# Test_Jig_Pixhawk_DUT.net
KiCad netlist of a schematic drawn in Altium Designer
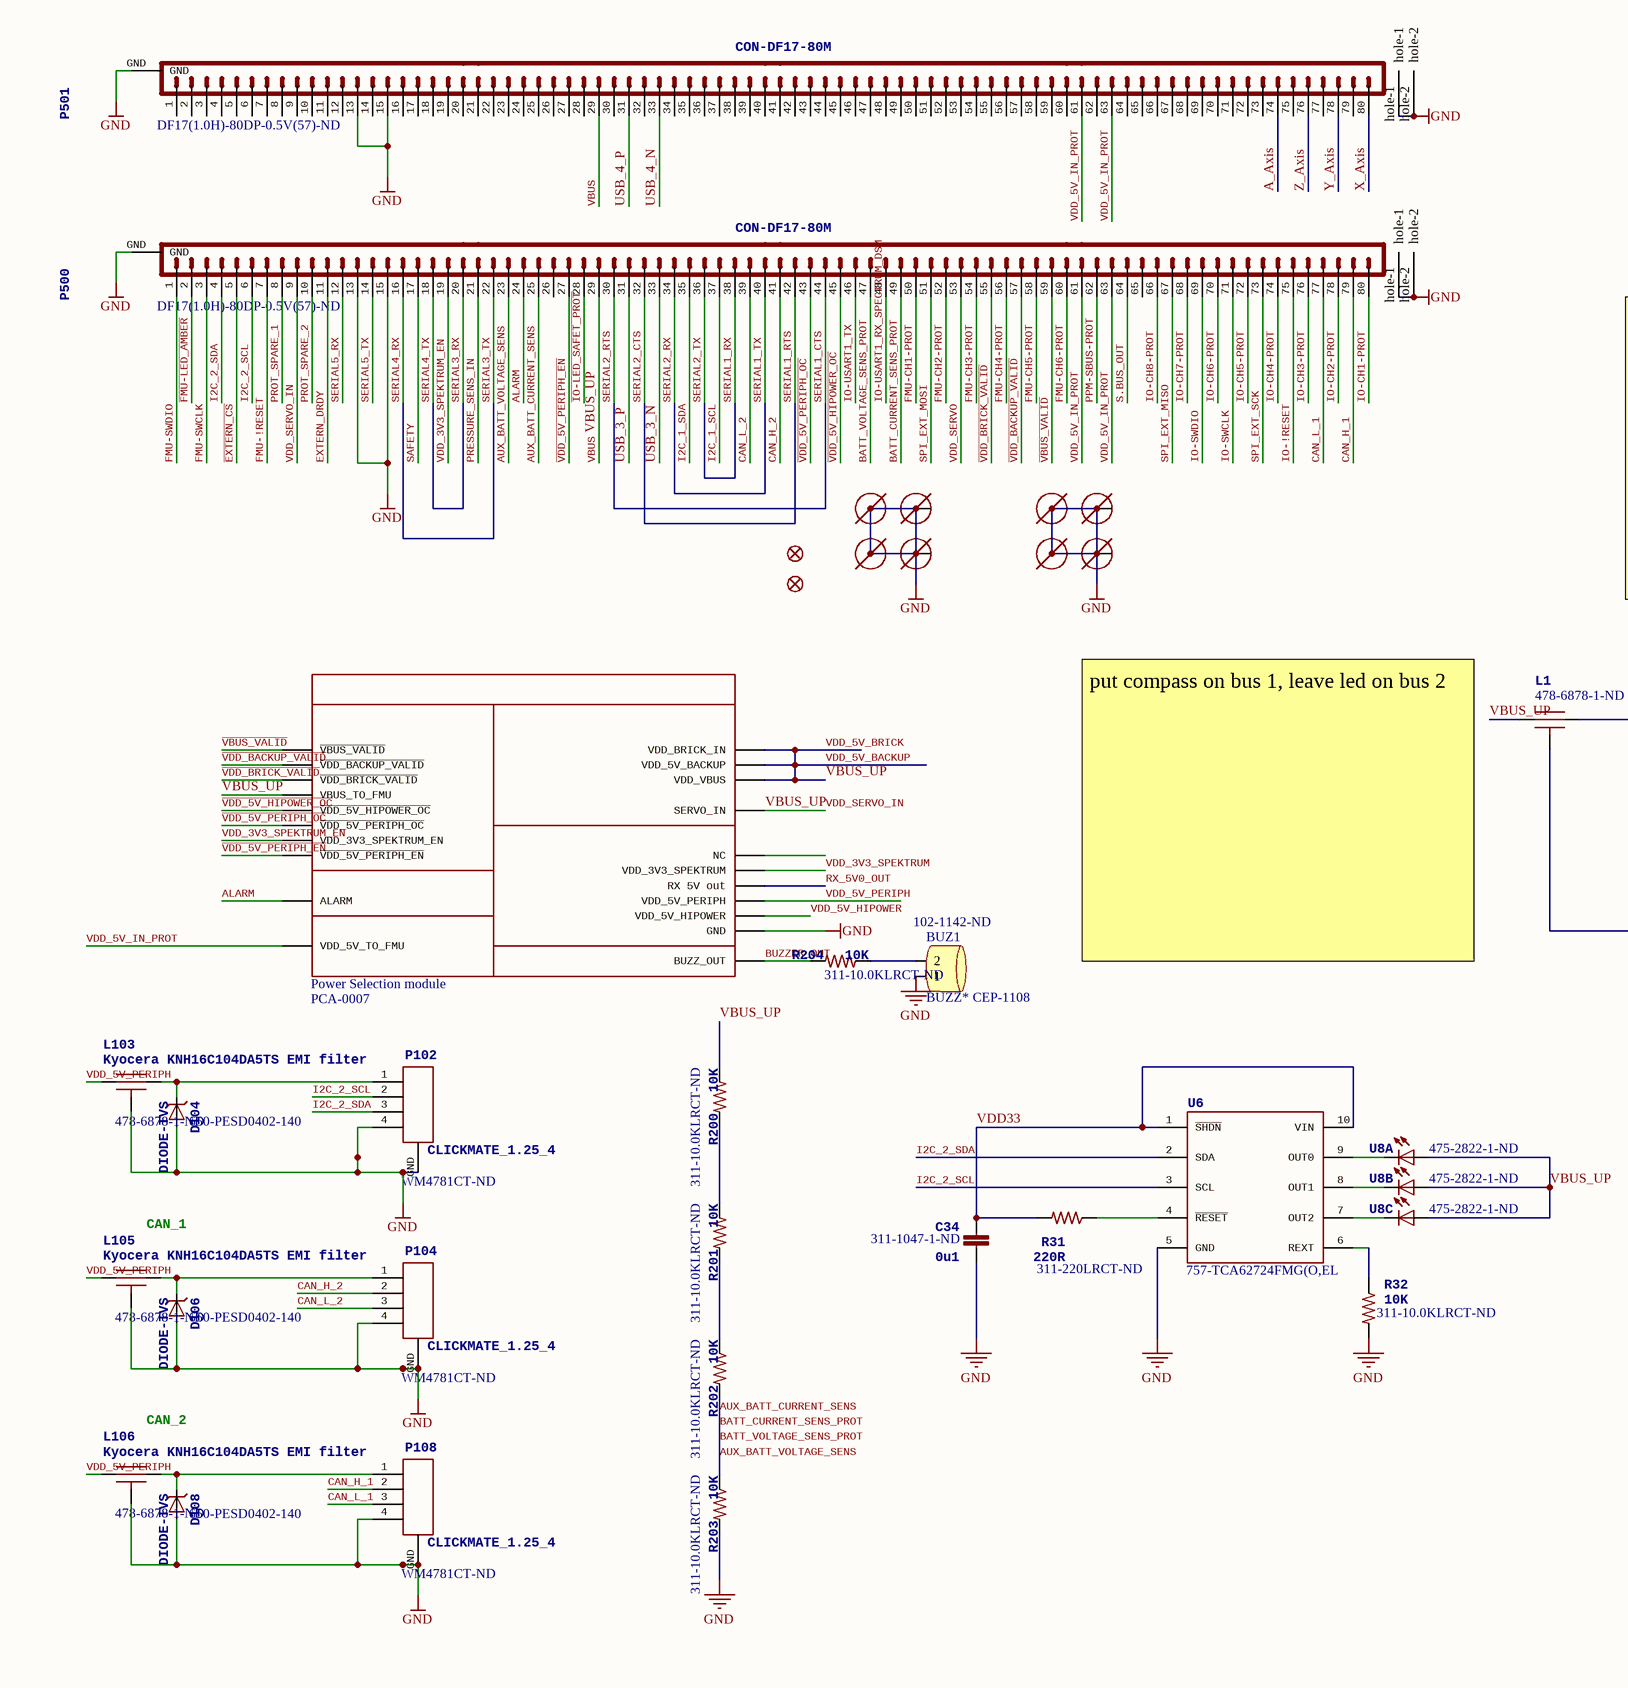
[diagram p0: Test_Jig_Pixhawk_DUT.SchDoc, left]
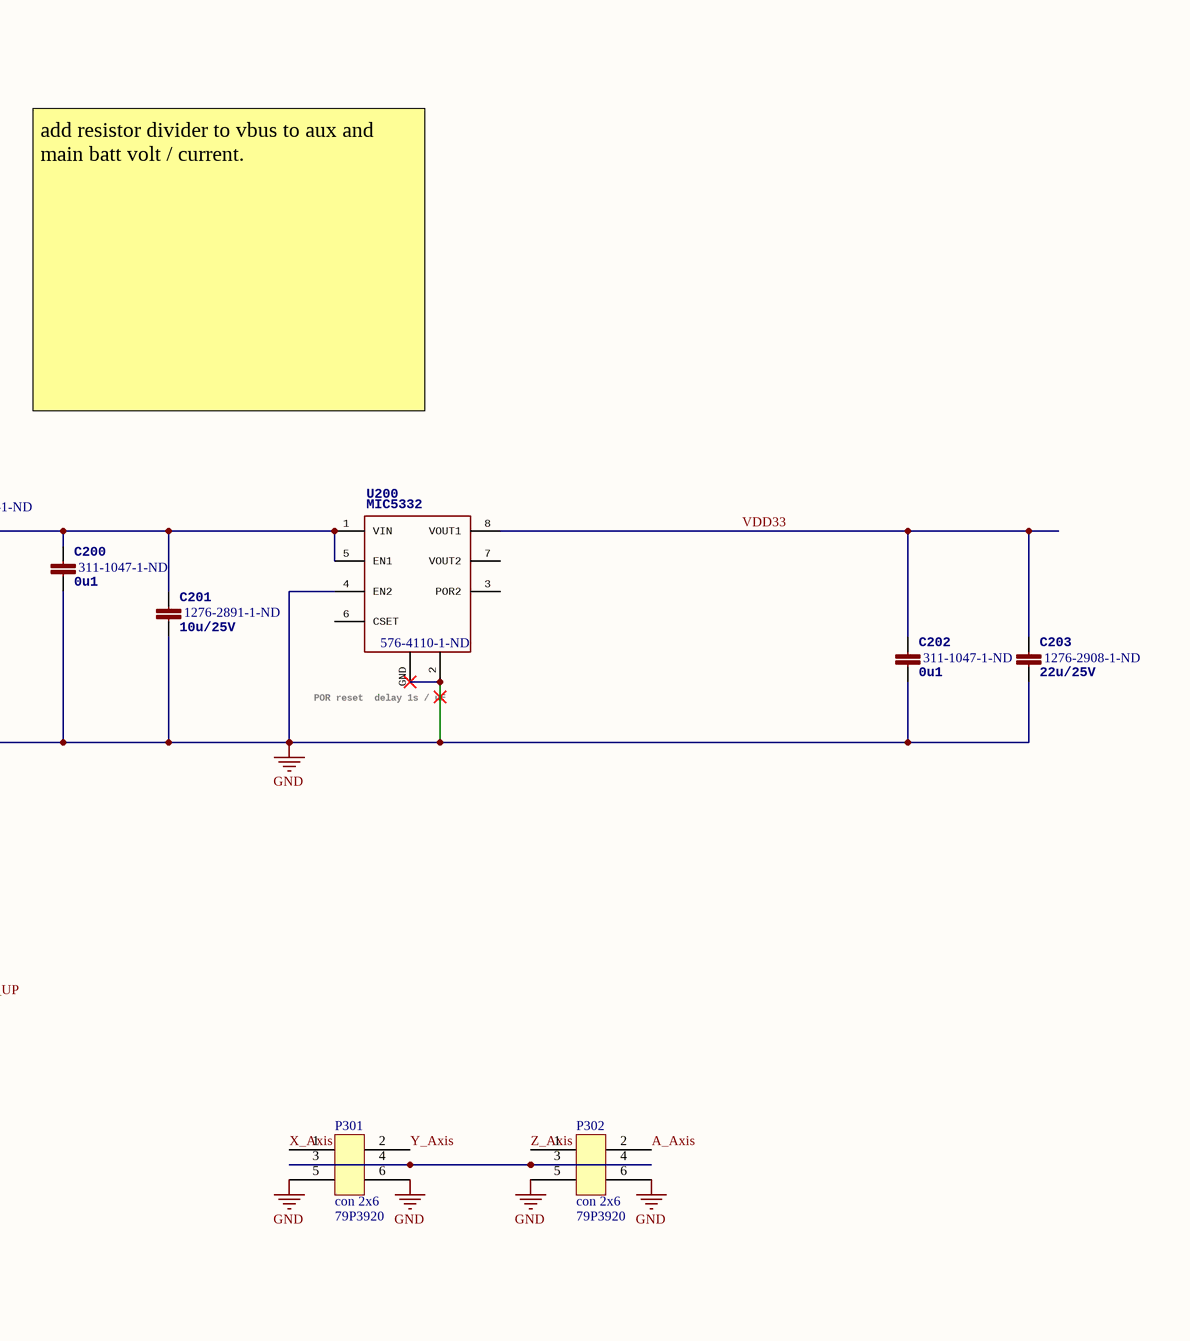
[diagram p1: Test_Jig_Pixhawk_DUT.SchDoc, right]

(export (version "E")
  (design (tool "Eeschema 10.0.6"))
  (components
    (comp (ref "BUZ1")
      (value "BUZZ* CEP-1108")
      (footprint "CEP-1108")
      (fields (field (name "MANUFACTURER") "CUI") (field (name "SUPPLIER PART NUMBER 1") "102-1142-ND"))
      (libsource (lib "LimeLab Integrated Lib R1") (part "BUZZ* CEP-1108"))
    )
    (comp (ref "C34")
      (value "0u1")
      (footprint "0402-CAP")
      (fields
        (field (name "PARTNO") "CC0402ZRY5V7BB104")
        (field (name "SUPPLIER PART NUMBER 1") "311-1047-1-ND")
      )
      (libsource (lib "pixhawk2") (part "CAP0402"))
    )
    (comp (ref "C200")
      (value "0u1")
      (footprint "0402-CAP")
      (fields (field (name "SUPPLIER PART NUMBER 1") "311-1047-1-ND"))
      (libsource (lib "") (part "CAP0402_1"))
    )
    (comp (ref "C201")
      (value "10u/25V")
      (footprint "0805-CAP")
      (fields (field (name "SUPPLIER PART NUMBER 1") "1276-2891-1-ND"))
      (libsource (lib "pixhawk2") (part "CAP0805"))
    )
    (comp (ref "C202")
      (value "0u1")
      (footprint "0402-CAP")
      (fields (field (name "SUPPLIER PART NUMBER 1") "311-1047-1-ND"))
      (libsource (lib "") (part "CAP0402_1"))
    )
    (comp (ref "C203")
      (value "22u/25V")
      (footprint "0805-CAP")
      (fields (field (name "SUPPLIER PART NUMBER 1") "1276-2908-1-ND"))
      (libsource (lib "pixhawk2") (part "CAP0805"))
    )
    (comp (ref "D104")
      (value "DIODE-TVS")
      (footprint "0402-TVS")
      (description "Diode, TVS, 14VWM, 40VC, 0402, SMD")
      (fields
        (field (name "SUPPLIER PART NUMBER 1") "650-PESD0402-140")
        (field (name "3DR_PARTNO") "ECM0837")
      )
      (libsource (lib "PCA_0005_FULL_CB_REV_A") (part "DIODE-TVS"))
    )
    (comp (ref "D106")
      (value "DIODE-TVS")
      (footprint "0402-TVS")
      (description "Diode, TVS, 14VWM, 40VC, 0402, SMD")
      (fields
        (field (name "SUPPLIER PART NUMBER 1") "650-PESD0402-140")
        (field (name "3DR_PARTNO") "ECM0837")
      )
      (libsource (lib "PCA_0005_FULL_CB_REV_A") (part "DIODE-TVS"))
    )
    (comp (ref "D108")
      (value "DIODE-TVS")
      (footprint "0402-TVS")
      (description "Diode, TVS, 14VWM, 40VC, 0402, SMD")
      (fields
        (field (name "SUPPLIER PART NUMBER 1") "650-PESD0402-140")
        (field (name "3DR_PARTNO") "ECM0837")
      )
      (libsource (lib "PCA_0005_FULL_CB_REV_A") (part "DIODE-TVS"))
    )
    (comp (ref "JP400")
      (value "FIDUCIAL1.5X3")
      (footprint "FIDUCIAL-1.5X3")
      (description "<b>Fiducial Alignment Points</b>\nVarious fiducial points for machine vision alignment.")
      (libsource (lib "pixhawk2") (part "FIDUCIAL1.5X3"))
    )
    (comp (ref "JP401")
      (value "FIDUCIAL1.5X3")
      (footprint "FIDUCIAL-1.5X3")
      (description "<b>Fiducial Alignment Points</b>\nVarious fiducial points for machine vision alignment.")
      (libsource (lib "pixhawk2") (part "FIDUCIAL1.5X3"))
    )
    (comp (ref "L1")
      (value "Kyocera KNH16C104DA5TS EMI filter")
      (footprint "KYOCERA-KNH16-DA")
      (fields (field (name "SUPPLIER PART NUMBER 1") "478-6878-1-ND"))
      (libsource (lib "pixhawk2") (part "KNH16C104DA5TS"))
    )
    (comp (ref "L103")
      (value "Kyocera KNH16C104DA5TS EMI filter")
      (footprint "KYOCERA-KNH16-DA")
      (description "Capacitor, Filter, 0.1uF, 25V, 2A, 0603, SMD")
      (fields (field (name "SUPPLIER PART NUMBER 1") "478-6878-1-ND") (field (name "3DR_PARTNO") "ECM0719"))
      (libsource (lib "PCA_0005_FULL_CB_REV_A") (part "KNH16C104DA5TS"))
    )
    (comp (ref "L105")
      (value "Kyocera KNH16C104DA5TS EMI filter")
      (footprint "KYOCERA-KNH16-DA")
      (description "Capacitor, Filter, 0.1uF, 25V, 2A, 0603, SMD")
      (fields (field (name "SUPPLIER PART NUMBER 1") "478-6878-1-ND") (field (name "3DR_PARTNO") "ECM0719"))
      (libsource (lib "PCA_0005_FULL_CB_REV_A") (part "KNH16C104DA5TS"))
    )
    (comp (ref "L106")
      (value "Kyocera KNH16C104DA5TS EMI filter")
      (footprint "KYOCERA-KNH16-DA")
      (description "Capacitor, Filter, 0.1uF, 25V, 2A, 0603, SMD")
      (fields (field (name "SUPPLIER PART NUMBER 1") "478-6878-1-ND") (field (name "3DR_PARTNO") "ECM0719"))
      (libsource (lib "PCA_0005_FULL_CB_REV_A") (part "KNH16C104DA5TS"))
    )
    (comp (ref "M3_MOUNT901")
      (value "MOUNT-HOLE1.8MM")
      (footprint "MOUNT-HOLE1.8")
      (libsource (lib "pixhawk2") (part "MOUNT-HOLE1.8MM"))
    )
    (comp (ref "M3_MOUNT902")
      (value "MOUNT-HOLE1.8MM")
      (footprint "MOUNT-HOLE1.8")
      (libsource (lib "pixhawk2") (part "MOUNT-HOLE1.8MM"))
    )
    (comp (ref "M3_MOUNT903")
      (value "MOUNT-HOLE1.8MM")
      (footprint "MOUNT-HOLE1.8")
      (libsource (lib "pixhawk2") (part "MOUNT-HOLE1.8MM"))
    )
    (comp (ref "M3_MOUNT904")
      (value "MOUNT-HOLE1.8MM")
      (footprint "MOUNT-HOLE1.8")
      (libsource (lib "pixhawk2") (part "MOUNT-HOLE1.8MM"))
    )
    (comp (ref "M3_MOUNT911")
      (value "MOUNT-HOLE1.8MM")
      (footprint "MOUNT-HOLE1.8")
      (libsource (lib "pixhawk2") (part "MOUNT-HOLE1.8MM"))
    )
    (comp (ref "M3_MOUNT912")
      (value "MOUNT-HOLE1.8MM")
      (footprint "MOUNT-HOLE1.8")
      (libsource (lib "pixhawk2") (part "MOUNT-HOLE1.8MM"))
    )
    (comp (ref "M3_MOUNT913")
      (value "MOUNT-HOLE1.8MM")
      (footprint "MOUNT-HOLE1.8")
      (libsource (lib "pixhawk2") (part "MOUNT-HOLE1.8MM"))
    )
    (comp (ref "M3_MOUNT914")
      (value "MOUNT-HOLE1.8MM")
      (footprint "MOUNT-HOLE1.8")
      (libsource (lib "pixhawk2") (part "MOUNT-HOLE1.8MM"))
    )
    (comp (ref "P102")
      (value "CLICKMATE_1.25_4")
      (footprint "CLICKMATE_V4")
      (description "Connector, Rcpt, 4Pos, 1.25MM, W/B, VERT, SMD, Tin")
      (fields (field (name "SUPPLIER PART NUMBER 1") "WM4781CT-ND") (field (name "3DR_PARTNO") "PRT0441"))
      (libsource (lib "PCA_0005_FULL_CB_REV_A") (part "CLICKMATE_1.25_4"))
    )
    (comp (ref "P104")
      (value "CLICKMATE_1.25_4")
      (footprint "CLICKMATE_V4")
      (description "Connector, Rcpt, 4Pos, 1.25MM, W/B, VERT, SMD, Tin")
      (fields (field (name "SUPPLIER PART NUMBER 1") "WM4781CT-ND") (field (name "3DR_PARTNO") "PRT0441"))
      (libsource (lib "PCA_0005_FULL_CB_REV_A") (part "CLICKMATE_1.25_4"))
    )
    (comp (ref "P108")
      (value "CLICKMATE_1.25_4")
      (footprint "CLICKMATE_V4")
      (description "Connector, Rcpt, 4Pos, 1.25MM, W/B, VERT, SMD, Tin")
      (fields (field (name "SUPPLIER PART NUMBER 1") "WM4781CT-ND") (field (name "3DR_PARTNO") "PRT0441"))
      (libsource (lib "PCA_0005_FULL_CB_REV_A") (part "CLICKMATE_1.25_4"))
    )
    (comp (ref "P301")
      (value "con 2x6")
      (footprint "TSW-103-07-G-D")
      (description "Connector, Header, 6Pos, 2.54MM, Vert, THT, Au")
      (fields (field (name "SUPPLIER PART NUMBER 1") "79P3920") (field (name "3DR_PARTNO") "PRT0445"))
      (libsource (lib "PCA_0005_FULL_CB_REV_A") (part "con 2x6"))
    )
    (comp (ref "P302")
      (value "con 2x6")
      (footprint "TSW-103-07-G-D")
      (description "Connector, Header, 6Pos, 2.54MM, Vert, THT, Au")
      (fields (field (name "SUPPLIER PART NUMBER 1") "79P3920") (field (name "3DR_PARTNO") "PRT0445"))
      (libsource (lib "PCA_0005_FULL_CB_REV_A") (part "con 2x6"))
    )
    (comp (ref "P500")
      (value "CON-DF17-80M")
      (footprint "CON-DF17-80M")
      (description "Connector, Header, 80Pos, .5MM, DUAL, SMD, Au")
      (fields
        (field (name "SUPPLIER PART NUMBER 1") "DF17(1.0H)-80DP-0.5V(57)-ND")
        (field (name "3DR_PARTNO") "PRT0436")
      )
      (libsource (lib "PCA_0005_FULL_CB_REV_A") (part "CON-DF17-80M"))
    )
    (comp (ref "P501")
      (value "CON-DF17-80M")
      (footprint "CON-DF17-80M")
      (description "Connector, Header, 80Pos, .5MM, DUAL, SMD, Au")
      (fields
        (field (name "SUPPLIER PART NUMBER 1") "DF17(1.0H)-80DP-0.5V(57)-ND")
        (field (name "3DR_PARTNO") "PRT0436")
      )
      (libsource (lib "PCA_0005_FULL_CB_REV_A") (part "CON-DF17-80M"))
    )
    (comp (ref "PSM200")
      (value "Power Selection module")
      (footprint "PSM")
      (description "PCA, PSM, PX4, Assembly")
      (fields (field (name "SUPPLIER PART NUMBER 1") "PCA-0007") (field (name "3DR_PARTNO") "PCA0007"))
      (libsource (lib "PCA_0005_FULL_CB_REV_A") (part "PSMPSM"))
    )
    (comp (ref "R31")
      (value "220R")
      (footprint "0402-RES")
      (fields (field (name "SUPPLIER PART NUMBER 1") "311-220LRCT-ND"))
      (libsource (lib "pixhawk2") (part "RESISTOR0402-RES"))
    )
    (comp (ref "R32")
      (value "10K")
      (footprint "0402-RES")
      (fields
        (field (name "PARTNO") "RC0402FR-0710KL")
        (field (name "SUPPLIER PART NUMBER 1") "311-10.0KLRCT-ND")
      )
      (libsource (lib "pixhawk2") (part "RESISTOR0402-RES"))
    )
    (comp (ref "R200")
      (value "10K")
      (footprint "0402-RES")
      (description "RES 10K OHM 1/16W 1% 0402 SMD")
      (fields
        (field (name "PARTNO") "RC0402FR-0710KL")
        (field (name "SUPPLIER PART NUMBER 1") "311-10.0KLRCT-ND")
        (field (name "3DR_PARTNO") "ECM0800")
      )
      (libsource (lib "pixhawk2") (part "RESISTOR0402-RES"))
    )
    (comp (ref "R201")
      (value "10K")
      (footprint "0402-RES")
      (description "RES 10K OHM 1/16W 1% 0402 SMD")
      (fields
        (field (name "PARTNO") "RC0402FR-0710KL")
        (field (name "SUPPLIER PART NUMBER 1") "311-10.0KLRCT-ND")
        (field (name "3DR_PARTNO") "ECM0800")
      )
      (libsource (lib "pixhawk2") (part "RESISTOR0402-RES"))
    )
    (comp (ref "R202")
      (value "10K")
      (footprint "0402-RES")
      (description "RES 10K OHM 1/16W 1% 0402 SMD")
      (fields
        (field (name "PARTNO") "RC0402FR-0710KL")
        (field (name "SUPPLIER PART NUMBER 1") "311-10.0KLRCT-ND")
        (field (name "3DR_PARTNO") "ECM0800")
      )
      (libsource (lib "pixhawk2") (part "RESISTOR0402-RES"))
    )
    (comp (ref "R203")
      (value "10K")
      (footprint "0402-RES")
      (description "RES 10K OHM 1/16W 1% 0402 SMD")
      (fields
        (field (name "PARTNO") "RC0402FR-0710KL")
        (field (name "SUPPLIER PART NUMBER 1") "311-10.0KLRCT-ND")
        (field (name "3DR_PARTNO") "ECM0800")
      )
      (libsource (lib "pixhawk2") (part "RESISTOR0402-RES"))
    )
    (comp (ref "R204")
      (value "10K")
      (footprint "0402-RES")
      (description "RES 10K OHM 1/16W 1% 0402 SMD")
      (fields
        (field (name "PARTNO") "RC0402FR-0710KL")
        (field (name "SUPPLIER PART NUMBER 1") "311-10.0KLRCT-ND")
        (field (name "3DR_PARTNO") "ECM0800")
      )
      (libsource (lib "pixhawk2") (part "RESISTOR0402-RES"))
    )
    (comp (ref "U6")
      (value "TCA62724FMG")
      (footprint "SON10")
      (description "Toshiba TCA62724FMG I2C RGB LED driver")
      (fields (field (name "SUPPLIER PART NUMBER 1") "757-TCA62724FMG(O,EL"))
      (libsource (lib "pixhawk2") (part "TCA62724FMG"))
    )
    (comp (ref "U8")
      (value "LRTB GFTG-T7AW-1+V7A7-29+R5T9-49-L")
      (footprint "6-PLCC")
      (description "RGB LED with separate anode/cathode terminals")
      (fields (field (name "SUPPLIER PART NUMBER 1") "475-2822-1-ND"))
      (libsource (lib "pixhawk2") (part "RGB-LED6-PLCC"))
    )
    (comp (ref "U200")
      (value "MIC5332")
      (footprint "MLF-8-EPAD")
      (fields (field (name "SUPPLIER PART NUMBER 1") "576-4110-1-ND"))
      (libsource (lib "pixhawk2") (part "MIC5332"))
    )
  )
  (nets
    (net (code "1") (name "/ALARM") (class "Default")
      (node (ref "P500") (pin "24") (pinfunction "24_24") (pintype "passive"))
      (node (ref "PSM200") (pin "ALARM") (pinfunction "ALARM_ALARM") (pintype "passive"))
    )
    (net (code "2") (name "/AUX_BATT_CURRENT_SENS") (class "Default")
      (node (ref "P500") (pin "23") (pinfunction "23_23") (pintype "passive"))
      (node (ref "P500") (pin "25") (pinfunction "25_25") (pintype "passive"))
      (node (ref "P500") (pin "47") (pinfunction "47_47") (pintype "passive"))
      (node (ref "P500") (pin "49") (pinfunction "49_49") (pintype "passive"))
      (node (ref "R202") (pin "P$2") (pinfunction "2_P$2") (pintype "passive"))
      (node (ref "R203") (pin "P$1") (pinfunction "1_P$1") (pintype "passive"))
    )
    (net (code "3") (name "/A_Axis") (class "Default")
      (node (ref "P302") (pin "2") (pinfunction "2_2") (pintype "passive"))
      (node (ref "P501") (pin "74") (pinfunction "74_74") (pintype "passive"))
    )
    (net (code "4") (name "/BUZZER_OUT") (class "Default")
      (node (ref "PSM200") (pin "BUZZER_OUT") (pinfunction "BUZZ_OUT_BUZZER_OUT") (pintype "passive"))
      (node (ref "R204") (pin "P$2") (pinfunction "2_P$2") (pintype "passive"))
    )
    (net (code "5") (name "/CAN_H_1") (class "Default")
      (node (ref "P108") (pin "2") (pinfunction "2_2") (pintype "passive"))
      (node (ref "P500") (pin "79") (pinfunction "79_79") (pintype "passive"))
    )
    (net (code "6") (name "/CAN_H_2") (class "Default")
      (node (ref "P104") (pin "2") (pinfunction "2_2") (pintype "passive"))
      (node (ref "P500") (pin "41") (pinfunction "41_41") (pintype "passive"))
    )
    (net (code "7") (name "/CAN_L_1") (class "Default")
      (node (ref "P108") (pin "3") (pinfunction "3_3") (pintype "passive"))
      (node (ref "P500") (pin "77") (pinfunction "77_77") (pintype "passive"))
    )
    (net (code "8") (name "/CAN_L_2") (class "Default")
      (node (ref "P104") (pin "3") (pinfunction "3_3") (pintype "passive"))
      (node (ref "P500") (pin "39") (pinfunction "39_39") (pintype "passive"))
    )
    (net (code "9") (name "/EXTERN_DRDY") (class "Default")
      (node (ref "P500") (pin "11") (pinfunction "11_11") (pintype "passive"))
    )
    (net (code "10") (name "/FMU-!RESET") (class "Default")
      (node (ref "P500") (pin "7") (pinfunction "7_7") (pintype "passive"))
    )
    (net (code "11") (name "/FMU-CH1-PROT") (class "Default")
      (node (ref "P500") (pin "50") (pinfunction "50_50") (pintype "passive"))
    )
    (net (code "12") (name "/FMU-CH2-PROT") (class "Default")
      (node (ref "P500") (pin "52") (pinfunction "52_52") (pintype "passive"))
    )
    (net (code "13") (name "/FMU-CH3-PROT") (class "Default")
      (node (ref "P500") (pin "54") (pinfunction "54_54") (pintype "passive"))
    )
    (net (code "14") (name "/FMU-CH4-PROT") (class "Default")
      (node (ref "P500") (pin "56") (pinfunction "56_56") (pintype "passive"))
    )
    (net (code "15") (name "/FMU-CH5-PROT") (class "Default")
      (node (ref "P500") (pin "58") (pinfunction "58_58") (pintype "passive"))
    )
    (net (code "16") (name "/FMU-CH6-PROT") (class "Default")
      (node (ref "P500") (pin "60") (pinfunction "60_60") (pintype "passive"))
    )
    (net (code "17") (name "/FMU-SWCLK") (class "Default")
      (node (ref "P500") (pin "3") (pinfunction "3_3") (pintype "passive"))
    )
    (net (code "18") (name "/FMU-SWDIO") (class "Default")
      (node (ref "P500") (pin "1") (pinfunction "1_1") (pintype "passive"))
    )
    (net (code "19") (name "/I2C_1_SCL") (class "Default")
      (node (ref "P500") (pin "37") (pinfunction "37_37") (pintype "passive"))
    )
    (net (code "20") (name "/I2C_1_SDA") (class "Default")
      (node (ref "P500") (pin "35") (pinfunction "35_35") (pintype "passive"))
    )
    (net (code "21") (name "/I2C_2_SCL") (class "Default")
      (node (ref "P102") (pin "2") (pinfunction "2_2") (pintype "passive"))
      (node (ref "P500") (pin "6") (pinfunction "6_6") (pintype "passive"))
      (node (ref "U6") (pin "3") (pinfunction "SCL_3") (pintype "passive"))
    )
    (net (code "22") (name "/I2C_2_SDA") (class "Default")
      (node (ref "P102") (pin "3") (pinfunction "3_3") (pintype "passive"))
      (node (ref "P500") (pin "4") (pinfunction "4_4") (pintype "passive"))
      (node (ref "U6") (pin "2") (pinfunction "SDA_2") (pintype "passive"))
    )
    (net (code "23") (name "/IO-!RESET") (class "Default")
      (node (ref "P500") (pin "75") (pinfunction "75_75") (pintype "passive"))
    )
    (net (code "24") (name "/IO-CH1-PROT") (class "Default")
      (node (ref "P500") (pin "80") (pinfunction "80_80") (pintype "passive"))
    )
    (net (code "25") (name "/IO-CH2-PROT") (class "Default")
      (node (ref "P500") (pin "78") (pinfunction "78_78") (pintype "passive"))
    )
    (net (code "26") (name "/IO-CH3-PROT") (class "Default")
      (node (ref "P500") (pin "76") (pinfunction "76_76") (pintype "passive"))
    )
    (net (code "27") (name "/IO-CH4-PROT") (class "Default")
      (node (ref "P500") (pin "74") (pinfunction "74_74") (pintype "passive"))
    )
    (net (code "28") (name "/IO-CH5-PROT") (class "Default")
      (node (ref "P500") (pin "72") (pinfunction "72_72") (pintype "passive"))
    )
    (net (code "29") (name "/IO-CH6-PROT") (class "Default")
      (node (ref "P500") (pin "70") (pinfunction "70_70") (pintype "passive"))
    )
    (net (code "30") (name "/IO-CH7-PROT") (class "Default")
      (node (ref "P500") (pin "68") (pinfunction "68_68") (pintype "passive"))
    )
    (net (code "31") (name "/IO-CH8-PROT") (class "Default")
      (node (ref "P500") (pin "66") (pinfunction "66_66") (pintype "passive"))
    )
    (net (code "32") (name "/IO-SWCLK") (class "Default")
      (node (ref "P500") (pin "71") (pinfunction "71_71") (pintype "passive"))
    )
    (net (code "33") (name "/IO-SWDIO") (class "Default")
      (node (ref "P500") (pin "69") (pinfunction "69_69") (pintype "passive"))
    )
    (net (code "34") (name "/IO-USART1_RX_SPECTRUM_DSM") (class "Default")
      (node (ref "P500") (pin "48") (pinfunction "48_48") (pintype "passive"))
    )
    (net (code "35") (name "/IO-USART1_TX") (class "Default")
      (node (ref "P500") (pin "46") (pinfunction "46_46") (pintype "passive"))
    )
    (net (code "36") (name "/PPM-SBUS-PROT") (class "Default")
      (node (ref "P500") (pin "62") (pinfunction "62_62") (pintype "passive"))
    )
    (net (code "37") (name "/PRESSURE_SENS_IN") (class "Default")
      (node (ref "P500") (pin "21") (pinfunction "21_21") (pintype "passive"))
    )
    (net (code "38") (name "/PROT_SPARE_1") (class "Default")
      (node (ref "P500") (pin "8") (pinfunction "8_8") (pintype "passive"))
    )
    (net (code "39") (name "/PROT_SPARE_2") (class "Default")
      (node (ref "P500") (pin "10") (pinfunction "10_10") (pintype "passive"))
    )
    (net (code "40") (name "/RX_5V0_OUT") (class "Default")
      (node (ref "PSM200") (pin "RX") (pinfunction "RX_5V_out_RX") (pintype "passive"))
    )
    (net (code "41") (name "/S.BUS_OUT") (class "Default")
      (node (ref "P500") (pin "64") (pinfunction "64_64") (pintype "passive"))
    )
    (net (code "42") (name "/SAFETY") (class "Default")
      (node (ref "P500") (pin "17") (pinfunction "17_17") (pintype "passive"))
    )
    (net (code "43") (name "/SERIAL1_CTS") (class "Default")
      (node (ref "P500") (pin "30") (pinfunction "30_30") (pintype "passive"))
      (node (ref "P500") (pin "44") (pinfunction "44_44") (pintype "passive"))
    )
    (net (code "44") (name "/SERIAL1_RTS") (class "Default")
      (node (ref "P500") (pin "32") (pinfunction "32_32") (pintype "passive"))
      (node (ref "P500") (pin "42") (pinfunction "42_42") (pintype "passive"))
    )
    (net (code "45") (name "/SERIAL1_RX") (class "Default")
      (node (ref "P500") (pin "36") (pinfunction "36_36") (pintype "passive"))
      (node (ref "P500") (pin "38") (pinfunction "38_38") (pintype "passive"))
    )
    (net (code "46") (name "/SERIAL1_TX") (class "Default")
      (node (ref "P500") (pin "34") (pinfunction "34_34") (pintype "passive"))
      (node (ref "P500") (pin "40") (pinfunction "40_40") (pintype "passive"))
    )
    (net (code "47") (name "/SERIAL3_RX") (class "Default")
      (node (ref "P500") (pin "18") (pinfunction "18_18") (pintype "passive"))
      (node (ref "P500") (pin "20") (pinfunction "20_20") (pintype "passive"))
    )
    (net (code "48") (name "/SERIAL3_TX") (class "Default")
      (node (ref "P500") (pin "16") (pinfunction "16_16") (pintype "passive"))
      (node (ref "P500") (pin "22") (pinfunction "22_22") (pintype "passive"))
    )
    (net (code "49") (name "/SERIAL5_RX") (class "Default")
      (node (ref "P500") (pin "12") (pinfunction "12_12") (pintype "passive"))
    )
    (net (code "50") (name "/SERIAL5_TX") (class "Default")
      (node (ref "P500") (pin "14") (pinfunction "14_14") (pintype "passive"))
    )
    (net (code "51") (name "/SPI_EXT_MISO") (class "Default")
      (node (ref "P500") (pin "67") (pinfunction "67_67") (pintype "passive"))
    )
    (net (code "52") (name "/SPI_EXT_MOSI") (class "Default")
      (node (ref "P500") (pin "51") (pinfunction "51_51") (pintype "passive"))
    )
    (net (code "53") (name "/SPI_EXT_SCK") (class "Default")
      (node (ref "P500") (pin "73") (pinfunction "73_73") (pintype "passive"))
    )
    (net (code "54") (name "/USB_3_N") (class "Default")
      (node (ref "P500") (pin "33") (pinfunction "33_33") (pintype "passive"))
    )
    (net (code "55") (name "/USB_3_P") (class "Default")
      (node (ref "P500") (pin "31") (pinfunction "31_31") (pintype "passive"))
    )
    (net (code "56") (name "/USB_4_N") (class "Default")
      (node (ref "P501") (pin "33") (pinfunction "33_33") (pintype "passive"))
    )
    (net (code "57") (name "/USB_4_P") (class "Default")
      (node (ref "P501") (pin "31") (pinfunction "31_31") (pintype "passive"))
    )
    (net (code "58") (name "/VBUS") (class "Default")
      (node (ref "L1") (pin "P$1") (pinfunction "P$1_P$1") (pintype "passive"))
      (node (ref "P500") (pin "29") (pinfunction "29_29") (pintype "passive"))
      (node (ref "P500") (pin "9") (pinfunction "9_9") (pintype "passive"))
      (node (ref "P501") (pin "29") (pinfunction "29_29") (pintype "passive"))
      (node (ref "PSM200") (pin "SERVO_IN") (pinfunction "SERVO_IN_SERVO_IN") (pintype "passive"))
      (node (ref "PSM200") (pin "VBUS") (pinfunction "VBUS_TO_FMU_VBUS") (pintype "passive"))
      (node (ref "PSM200") (pin "VDD_5V_BACKUP") (pinfunction "VDD_5V_BACKUP_VDD_5V_BACKUP") (pintype "passive"))
      (node (ref "PSM200") (pin "VDD_BRICK_IN") (pinfunction "VDD_BRICK_IN_VDD_BRICK_IN") (pintype "passive"))
      (node (ref "PSM200") (pin "VDD_VBUS") (pinfunction "VDD_VBUS_VDD_VBUS") (pintype "passive"))
      (node (ref "R200") (pin "P$1") (pinfunction "1_P$1") (pintype "passive"))
      (node (ref "U8") (pin "A1") (pinfunction "A_A1") (pintype "passive"))
      (node (ref "U8") (pin "A2") (pinfunction "A_A2") (pintype "passive"))
      (node (ref "U8") (pin "A3") (pinfunction "A_A3") (pintype "passive"))
    )
    (net (code "59") (name "/VDD33") (class "Default")
      (node (ref "C202") (pin "P$1") (pinfunction "1_P$1") (pintype "passive"))
      (node (ref "C203") (pin "P$1") (pinfunction "1_P$1") (pintype "passive"))
      (node (ref "C34") (pin "P$2") (pinfunction "2_P$2") (pintype "passive"))
      (node (ref "R31") (pin "P$2") (pinfunction "2_P$2") (pintype "passive"))
      (node (ref "U200") (pin "8") (pinfunction "VOUT1_8") (pintype "passive"))
      (node (ref "U6") (pin "1") (pinfunction "~{SHDN}_1") (pintype "passive"))
      (node (ref "U6") (pin "10") (pinfunction "VIN_10") (pintype "power_in"))
    )
    (net (code "60") (name "/VDD_3V3_SPEKTRUM") (class "Default")
      (node (ref "PSM200") (pin "SPEK") (pinfunction "VDD_3V3_SPEKTRUM_SPEK") (pintype "passive"))
    )
    (net (code "61") (name "/VDD_3V3_SPEKTRUM_EN") (class "Default")
      (node (ref "P500") (pin "19") (pinfunction "19_19") (pintype "passive"))
      (node (ref "PSM200") (pin "VDD_3V3_SPEKTRUM_EN") (pinfunction "VDD_3V3_SPEKTRUM_EN_VDD_3V3_SPEKTRUM_EN") (pintype "passive"))
    )
    (net (code "62") (name "/VDD_5V_HIPOWER") (class "Default")
      (node (ref "PSM200") (pin "5V_HIPOWER") (pinfunction "VDD_5V_HIPOWER_5V_HIPOWER") (pintype "passive"))
    )
    (net (code "63") (name "/VDD_5V_IN_PROT") (class "Default")
      (node (ref "P500") (pin "61") (pinfunction "61_61") (pintype "passive"))
      (node (ref "P500") (pin "63") (pinfunction "63_63") (pintype "passive"))
      (node (ref "P501") (pin "61") (pinfunction "61_61") (pintype "passive"))
      (node (ref "P501") (pin "63") (pinfunction "63_63") (pintype "passive"))
      (node (ref "PSM200") (pin "VDD_5V_IN_PROT") (pinfunction "VDD_5V_TO_FMU_VDD_5V_IN_PROT") (pintype "passive"))
    )
    (net (code "64") (name "/VDD_5V_PERIPH") (class "Default")
      (node (ref "L103") (pin "P$1") (pinfunction "P$1_P$1") (pintype "passive"))
      (node (ref "L105") (pin "P$1") (pinfunction "P$1_P$1") (pintype "passive"))
      (node (ref "L106") (pin "P$1") (pinfunction "P$1_P$1") (pintype "passive"))
      (node (ref "PSM200") (pin "5V_PERIPH") (pinfunction "VDD_5V_PERIPH_5V_PERIPH") (pintype "passive"))
    )
    (net (code "65") (name "/VDD_SERVO") (class "Default")
      (node (ref "P500") (pin "53") (pinfunction "53_53") (pintype "passive"))
    )
    (net (code "66") (name "/X_Axis") (class "Default")
      (node (ref "P301") (pin "1") (pinfunction "1_1") (pintype "passive"))
      (node (ref "P501") (pin "80") (pinfunction "80_80") (pintype "passive"))
    )
    (net (code "67") (name "/Y_Axis") (class "Default")
      (node (ref "P301") (pin "2") (pinfunction "2_2") (pintype "passive"))
      (node (ref "P501") (pin "78") (pinfunction "78_78") (pintype "passive"))
    )
    (net (code "68") (name "/Z_Axis") (class "Default")
      (node (ref "P302") (pin "1") (pinfunction "1_1") (pintype "passive"))
      (node (ref "P501") (pin "76") (pinfunction "76_76") (pintype "passive"))
    )
    (net (code "69") (name "/~{EXTERN_CS}") (class "Default")
      (node (ref "P500") (pin "5") (pinfunction "5_5") (pintype "passive"))
    )
    (net (code "70") (name "/~{FMU-LED_AMBER}") (class "Default")
      (node (ref "P500") (pin "2") (pinfunction "2_2") (pintype "passive"))
    )
    (net (code "71") (name "/~{IO-LED_SAFET_PROT}") (class "Default")
      (node (ref "P500") (pin "28") (pinfunction "28_28") (pintype "passive"))
    )
    (net (code "72") (name "/~{VBUS_VALID}") (class "Default")
      (node (ref "P500") (pin "59") (pinfunction "59_59") (pintype "passive"))
      (node (ref "PSM200") (pin "!VBUS_VALID") (pinfunction "~{VBUS_VALID}_!VBUS_VALID") (pintype "passive"))
    )
    (net (code "73") (name "/~{VDD_5V_HIPOWER_OC}") (class "Default")
      (node (ref "P500") (pin "45") (pinfunction "45_45") (pintype "passive"))
      (node (ref "PSM200") (pin "!VDD_5V_HIPOWER_OC") (pinfunction "~{VDD_5V_HIPOWER_OC}_!VDD_5V_HIPOWER_OC") (pintype "passive"))
    )
    (net (code "74") (name "/~{VDD_5V_PERIPH_EN}") (class "Default")
      (node (ref "P500") (pin "27") (pinfunction "27_27") (pintype "passive"))
      (node (ref "PSM200") (pin "!VDD_5V_PERIPH_EN") (pinfunction "~{VDD_5V_PERIPH_EN}_!VDD_5V_PERIPH_EN") (pintype "passive"))
    )
    (net (code "75") (name "/~{VDD_5V_PERIPH_OC}") (class "Default")
      (node (ref "P500") (pin "43") (pinfunction "43_43") (pintype "passive"))
      (node (ref "PSM200") (pin "!VDD_5V_PERIPH_OC") (pinfunction "~{VDD_5V_PERIPH_OC}_!VDD_5V_PERIPH_OC") (pintype "passive"))
    )
    (net (code "76") (name "/~{VDD_BACKUP_VALID}") (class "Default")
      (node (ref "P500") (pin "57") (pinfunction "57_57") (pintype "passive"))
      (node (ref "PSM200") (pin "!VDD_BACKUP_VALID") (pinfunction "~{VDD_BACKUP_VALID}_!VDD_BACKUP_VALID") (pintype "passive"))
    )
    (net (code "77") (name "/~{VDD_BRICK_VALID}") (class "Default")
      (node (ref "P500") (pin "55") (pinfunction "55_55") (pintype "passive"))
      (node (ref "PSM200") (pin "!VDD_BRICK_VALID") (pinfunction "~{VDD_BRICK_VALID}_!VDD_BRICK_VALID") (pintype "passive"))
    )
    (net (code "78") (name "GND") (class "Default")
      (node (ref "BUZ1") (pin "1") (pinfunction "1_1") (pintype "passive"))
      (node (ref "C200") (pin "P$2") (pinfunction "2_P$2") (pintype "passive"))
      (node (ref "C201") (pin "P$2") (pinfunction "2_P$2") (pintype "passive"))
      (node (ref "C202") (pin "P$2") (pinfunction "2_P$2") (pintype "passive"))
      (node (ref "C203") (pin "P$2") (pinfunction "2_P$2") (pintype "passive"))
      (node (ref "C34") (pin "P$1") (pinfunction "1_P$1") (pintype "passive"))
      (node (ref "D104") (pin "A") (pinfunction "A_A") (pintype "passive"))
      (node (ref "D106") (pin "A") (pinfunction "A_A") (pintype "passive"))
      (node (ref "D108") (pin "A") (pinfunction "A_A") (pintype "passive"))
      (node (ref "L1") (pin "GND") (pinfunction "GND_GND") (pintype "passive"))
      (node (ref "L103") (pin "GND") (pinfunction "GND_GND") (pintype "passive"))
      (node (ref "L105") (pin "GND") (pinfunction "GND_GND") (pintype "passive"))
      (node (ref "L106") (pin "GND") (pinfunction "GND_GND") (pintype "passive"))
      (node (ref "M3_MOUNT901") (pin "1") (pinfunction "1_1") (pintype "passive"))
      (node (ref "M3_MOUNT902") (pin "1") (pinfunction "1_1") (pintype "passive"))
      (node (ref "M3_MOUNT903") (pin "1") (pinfunction "1_1") (pintype "passive"))
      (node (ref "M3_MOUNT904") (pin "1") (pinfunction "1_1") (pintype "passive"))
      (node (ref "M3_MOUNT911") (pin "1") (pinfunction "1_1") (pintype "passive"))
      (node (ref "M3_MOUNT912") (pin "1") (pinfunction "1_1") (pintype "passive"))
      (node (ref "M3_MOUNT913") (pin "1") (pinfunction "1_1") (pintype "passive"))
      (node (ref "M3_MOUNT914") (pin "1") (pinfunction "1_1") (pintype "passive"))
      (node (ref "P102") (pin "4") (pinfunction "4_4") (pintype "passive"))
      (node (ref "P102") (pin "GND") (pinfunction "GND_GND") (pintype "passive"))
      (node (ref "P104") (pin "4") (pinfunction "4_4") (pintype "passive"))
      (node (ref "P104") (pin "GND") (pinfunction "GND_GND") (pintype "passive"))
      (node (ref "P108") (pin "4") (pinfunction "4_4") (pintype "passive"))
      (node (ref "P108") (pin "GND") (pinfunction "GND_GND") (pintype "passive"))
      (node (ref "P301") (pin "5") (pinfunction "5_5") (pintype "passive"))
      (node (ref "P301") (pin "6") (pinfunction "6_6") (pintype "passive"))
      (node (ref "P302") (pin "5") (pinfunction "5_5") (pintype "passive"))
      (node (ref "P302") (pin "6") (pinfunction "6_6") (pintype "passive"))
      (node (ref "P500") (pin "13") (pinfunction "13_13") (pintype "passive"))
      (node (ref "P500") (pin "15") (pinfunction "15_15") (pintype "passive"))
      (node (ref "P500") (pin "GND") (pinfunction "GND_GND") (pintype "passive"))
      (node (ref "P500") (pin "hole-1") (pinfunction "hole-1_hole-1") (pintype "passive"))
      (node (ref "P500") (pin "hole-2") (pinfunction "hole-2_hole-2") (pintype "passive"))
      (node (ref "P501") (pin "13") (pinfunction "13_13") (pintype "passive"))
      (node (ref "P501") (pin "15") (pinfunction "15_15") (pintype "passive"))
      (node (ref "P501") (pin "GND") (pinfunction "GND_GND") (pintype "passive"))
      (node (ref "P501") (pin "hole-1") (pinfunction "hole-1_hole-1") (pintype "passive"))
      (node (ref "P501") (pin "hole-2") (pinfunction "hole-2_hole-2") (pintype "passive"))
      (node (ref "PSM200") (pin "GND") (pinfunction "GND_GND") (pintype "passive"))
      (node (ref "R203") (pin "P$2") (pinfunction "2_P$2") (pintype "passive"))
      (node (ref "R32") (pin "P$2") (pinfunction "2_P$2") (pintype "passive"))
      (node (ref "U200") (pin "2") (pinfunction "GND_2") (pintype "power_in"))
      (node (ref "U200") (pin "4") (pinfunction "EN2_4") (pintype "passive"))
      (node (ref "U200") (pin "GND") (pinfunction "GND_GND") (pintype "power_in"))
      (node (ref "U6") (pin "5") (pinfunction "GND_5") (pintype "power_in"))
    )
    (net (code "79") (name "Net-(C200-1)") (class "Default")
      (node (ref "C200") (pin "P$1") (pinfunction "1_P$1") (pintype "passive"))
      (node (ref "C201") (pin "P$1") (pinfunction "1_P$1") (pintype "passive"))
      (node (ref "L1") (pin "P$2") (pinfunction "P$2_P$2") (pintype "passive"))
      (node (ref "U200") (pin "1") (pinfunction "VIN_1") (pintype "passive"))
      (node (ref "U200") (pin "5") (pinfunction "EN1_5") (pintype "passive"))
    )
    (net (code "80") (name "Net-(D104-PadC)") (class "Default")
      (node (ref "D104") (pin "C") (pinfunction "C_C") (pintype "passive"))
      (node (ref "L103") (pin "P$2") (pinfunction "P$2_P$2") (pintype "passive"))
      (node (ref "P102") (pin "1") (pinfunction "1_1") (pintype "passive"))
    )
    (net (code "81") (name "Net-(D106-PadC)") (class "Default")
      (node (ref "D106") (pin "C") (pinfunction "C_C") (pintype "passive"))
      (node (ref "L105") (pin "P$2") (pinfunction "P$2_P$2") (pintype "passive"))
      (node (ref "P104") (pin "1") (pinfunction "1_1") (pintype "passive"))
    )
    (net (code "82") (name "Net-(D108-PadC)") (class "Default")
      (node (ref "D108") (pin "C") (pinfunction "C_C") (pintype "passive"))
      (node (ref "L106") (pin "P$2") (pinfunction "P$2_P$2") (pintype "passive"))
      (node (ref "P108") (pin "1") (pinfunction "1_1") (pintype "passive"))
    )
    (net (code "83") (name "Net-(P301-Pad3)") (class "Default")
      (node (ref "P301") (pin "3") (pinfunction "3_3") (pintype "passive"))
      (node (ref "P301") (pin "4") (pinfunction "4_4") (pintype "passive"))
      (node (ref "P302") (pin "3") (pinfunction "3_3") (pintype "passive"))
      (node (ref "P302") (pin "4") (pinfunction "4_4") (pintype "passive"))
    )
    (net (code "84") (name "Net-(R31-1)") (class "Default")
      (node (ref "R31") (pin "P$1") (pinfunction "1_P$1") (pintype "passive"))
      (node (ref "U6") (pin "4") (pinfunction "~{RESET}_4") (pintype "passive"))
    )
    (net (code "85") (name "Net-(R32-1)") (class "Default")
      (node (ref "R32") (pin "P$1") (pinfunction "1_P$1") (pintype "passive"))
      (node (ref "U6") (pin "6") (pinfunction "REXT_6") (pintype "passive"))
    )
    (net (code "86") (name "Net-(R200-2)") (class "Default")
      (node (ref "R200") (pin "P$2") (pinfunction "2_P$2") (pintype "passive"))
      (node (ref "R201") (pin "P$1") (pinfunction "1_P$1") (pintype "passive"))
    )
    (net (code "87") (name "Net-(R201-2)") (class "Default")
      (node (ref "R201") (pin "P$2") (pinfunction "2_P$2") (pintype "passive"))
      (node (ref "R202") (pin "P$1") (pinfunction "1_P$1") (pintype "passive"))
    )
    (net (code "88") (name "Net-(R204-1)") (class "Default")
      (node (ref "BUZ1") (pin "2") (pinfunction "2_2") (pintype "passive"))
      (node (ref "R204") (pin "P$1") (pinfunction "1_P$1") (pintype "passive"))
    )
    (net (code "89") (name "Net-(U6-OUT0)") (class "Default")
      (node (ref "U6") (pin "9") (pinfunction "OUT0_9") (pintype "open_collector"))
      (node (ref "U8") (pin "C1") (pinfunction "C_C1") (pintype "passive"))
    )
    (net (code "90") (name "Net-(U6-OUT1)") (class "Default")
      (node (ref "U6") (pin "8") (pinfunction "OUT1_8") (pintype "open_collector"))
      (node (ref "U8") (pin "C2") (pinfunction "C_C2") (pintype "passive"))
    )
    (net (code "91") (name "Net-(U6-OUT2)") (class "Default")
      (node (ref "U6") (pin "7") (pinfunction "OUT2_7") (pintype "open_collector"))
      (node (ref "U8") (pin "C3") (pinfunction "C_C3") (pintype "passive"))
    )
    (net (code "92") (name "unconnected-(P500-Pad26)") (class "Default")
      (node (ref "P500") (pin "26") (pinfunction "26_26") (pintype "passive"))
    )
    (net (code "93") (name "unconnected-(P500-Pad65)") (class "Default")
      (node (ref "P500") (pin "65") (pinfunction "65_65") (pintype "passive"))
    )
    (net (code "94") (name "unconnected-(P501-Pad1)") (class "Default")
      (node (ref "P501") (pin "1") (pinfunction "1_1") (pintype "passive"))
    )
    (net (code "95") (name "unconnected-(P501-Pad2)") (class "Default")
      (node (ref "P501") (pin "2") (pinfunction "2_2") (pintype "passive"))
    )
    (net (code "96") (name "unconnected-(P501-Pad3)") (class "Default")
      (node (ref "P501") (pin "3") (pinfunction "3_3") (pintype "passive"))
    )
    (net (code "97") (name "unconnected-(P501-Pad4)") (class "Default")
      (node (ref "P501") (pin "4") (pinfunction "4_4") (pintype "passive"))
    )
    (net (code "98") (name "unconnected-(P501-Pad5)") (class "Default")
      (node (ref "P501") (pin "5") (pinfunction "5_5") (pintype "passive"))
    )
    (net (code "99") (name "unconnected-(P501-Pad6)") (class "Default")
      (node (ref "P501") (pin "6") (pinfunction "6_6") (pintype "passive"))
    )
    (net (code "100") (name "unconnected-(P501-Pad7)") (class "Default")
      (node (ref "P501") (pin "7") (pinfunction "7_7") (pintype "passive"))
    )
    (net (code "101") (name "unconnected-(P501-Pad8)") (class "Default")
      (node (ref "P501") (pin "8") (pinfunction "8_8") (pintype "passive"))
    )
    (net (code "102") (name "unconnected-(P501-Pad9)") (class "Default")
      (node (ref "P501") (pin "9") (pinfunction "9_9") (pintype "passive"))
    )
    (net (code "103") (name "unconnected-(P501-Pad10)") (class "Default")
      (node (ref "P501") (pin "10") (pinfunction "10_10") (pintype "passive"))
    )
    (net (code "104") (name "unconnected-(P501-Pad11)") (class "Default")
      (node (ref "P501") (pin "11") (pinfunction "11_11") (pintype "passive"))
    )
    (net (code "105") (name "unconnected-(P501-Pad12)") (class "Default")
      (node (ref "P501") (pin "12") (pinfunction "12_12") (pintype "passive"))
    )
    (net (code "106") (name "unconnected-(P501-Pad14)") (class "Default")
      (node (ref "P501") (pin "14") (pinfunction "14_14") (pintype "passive"))
    )
    (net (code "107") (name "unconnected-(P501-Pad16)") (class "Default")
      (node (ref "P501") (pin "16") (pinfunction "16_16") (pintype "passive"))
    )
    (net (code "108") (name "unconnected-(P501-Pad17)") (class "Default")
      (node (ref "P501") (pin "17") (pinfunction "17_17") (pintype "passive"))
    )
    (net (code "109") (name "unconnected-(P501-Pad18)") (class "Default")
      (node (ref "P501") (pin "18") (pinfunction "18_18") (pintype "passive"))
    )
    (net (code "110") (name "unconnected-(P501-Pad19)") (class "Default")
      (node (ref "P501") (pin "19") (pinfunction "19_19") (pintype "passive"))
    )
    (net (code "111") (name "unconnected-(P501-Pad20)") (class "Default")
      (node (ref "P501") (pin "20") (pinfunction "20_20") (pintype "passive"))
    )
    (net (code "112") (name "unconnected-(P501-Pad21)") (class "Default")
      (node (ref "P501") (pin "21") (pinfunction "21_21") (pintype "passive"))
    )
    (net (code "113") (name "unconnected-(P501-Pad22)") (class "Default")
      (node (ref "P501") (pin "22") (pinfunction "22_22") (pintype "passive"))
    )
    (net (code "114") (name "unconnected-(P501-Pad23)") (class "Default")
      (node (ref "P501") (pin "23") (pinfunction "23_23") (pintype "passive"))
    )
    (net (code "115") (name "unconnected-(P501-Pad24)") (class "Default")
      (node (ref "P501") (pin "24") (pinfunction "24_24") (pintype "passive"))
    )
    (net (code "116") (name "unconnected-(P501-Pad25)") (class "Default")
      (node (ref "P501") (pin "25") (pinfunction "25_25") (pintype "passive"))
    )
    (net (code "117") (name "unconnected-(P501-Pad26)") (class "Default")
      (node (ref "P501") (pin "26") (pinfunction "26_26") (pintype "passive"))
    )
    (net (code "118") (name "unconnected-(P501-Pad27)") (class "Default")
      (node (ref "P501") (pin "27") (pinfunction "27_27") (pintype "passive"))
    )
    (net (code "119") (name "unconnected-(P501-Pad28)") (class "Default")
      (node (ref "P501") (pin "28") (pinfunction "28_28") (pintype "passive"))
    )
    (net (code "120") (name "unconnected-(P501-Pad30)") (class "Default")
      (node (ref "P501") (pin "30") (pinfunction "30_30") (pintype "passive"))
    )
    (net (code "121") (name "unconnected-(P501-Pad32)") (class "Default")
      (node (ref "P501") (pin "32") (pinfunction "32_32") (pintype "passive"))
    )
    (net (code "122") (name "unconnected-(P501-Pad34)") (class "Default")
      (node (ref "P501") (pin "34") (pinfunction "34_34") (pintype "passive"))
    )
    (net (code "123") (name "unconnected-(P501-Pad35)") (class "Default")
      (node (ref "P501") (pin "35") (pinfunction "35_35") (pintype "passive"))
    )
    (net (code "124") (name "unconnected-(P501-Pad36)") (class "Default")
      (node (ref "P501") (pin "36") (pinfunction "36_36") (pintype "passive"))
    )
    (net (code "125") (name "unconnected-(P501-Pad37)") (class "Default")
      (node (ref "P501") (pin "37") (pinfunction "37_37") (pintype "passive"))
    )
    (net (code "126") (name "unconnected-(P501-Pad38)") (class "Default")
      (node (ref "P501") (pin "38") (pinfunction "38_38") (pintype "passive"))
    )
    (net (code "127") (name "unconnected-(P501-Pad39)") (class "Default")
      (node (ref "P501") (pin "39") (pinfunction "39_39") (pintype "passive"))
    )
    (net (code "128") (name "unconnected-(P501-Pad40)") (class "Default")
      (node (ref "P501") (pin "40") (pinfunction "40_40") (pintype "passive"))
    )
    (net (code "129") (name "unconnected-(P501-Pad41)") (class "Default")
      (node (ref "P501") (pin "41") (pinfunction "41_41") (pintype "passive"))
    )
    (net (code "130") (name "unconnected-(P501-Pad42)") (class "Default")
      (node (ref "P501") (pin "42") (pinfunction "42_42") (pintype "passive"))
    )
    (net (code "131") (name "unconnected-(P501-Pad43)") (class "Default")
      (node (ref "P501") (pin "43") (pinfunction "43_43") (pintype "passive"))
    )
    (net (code "132") (name "unconnected-(P501-Pad44)") (class "Default")
      (node (ref "P501") (pin "44") (pinfunction "44_44") (pintype "passive"))
    )
    (net (code "133") (name "unconnected-(P501-Pad45)") (class "Default")
      (node (ref "P501") (pin "45") (pinfunction "45_45") (pintype "passive"))
    )
    (net (code "134") (name "unconnected-(P501-Pad46)") (class "Default")
      (node (ref "P501") (pin "46") (pinfunction "46_46") (pintype "passive"))
    )
    (net (code "135") (name "unconnected-(P501-Pad47)") (class "Default")
      (node (ref "P501") (pin "47") (pinfunction "47_47") (pintype "passive"))
    )
    (net (code "136") (name "unconnected-(P501-Pad48)") (class "Default")
      (node (ref "P501") (pin "48") (pinfunction "48_48") (pintype "passive"))
    )
    (net (code "137") (name "unconnected-(P501-Pad49)") (class "Default")
      (node (ref "P501") (pin "49") (pinfunction "49_49") (pintype "passive"))
    )
    (net (code "138") (name "unconnected-(P501-Pad50)") (class "Default")
      (node (ref "P501") (pin "50") (pinfunction "50_50") (pintype "passive"))
    )
    (net (code "139") (name "unconnected-(P501-Pad51)") (class "Default")
      (node (ref "P501") (pin "51") (pinfunction "51_51") (pintype "passive"))
    )
    (net (code "140") (name "unconnected-(P501-Pad52)") (class "Default")
      (node (ref "P501") (pin "52") (pinfunction "52_52") (pintype "passive"))
    )
    (net (code "141") (name "unconnected-(P501-Pad53)") (class "Default")
      (node (ref "P501") (pin "53") (pinfunction "53_53") (pintype "passive"))
    )
    (net (code "142") (name "unconnected-(P501-Pad54)") (class "Default")
      (node (ref "P501") (pin "54") (pinfunction "54_54") (pintype "passive"))
    )
    (net (code "143") (name "unconnected-(P501-Pad55)") (class "Default")
      (node (ref "P501") (pin "55") (pinfunction "55_55") (pintype "passive"))
    )
    (net (code "144") (name "unconnected-(P501-Pad56)") (class "Default")
      (node (ref "P501") (pin "56") (pinfunction "56_56") (pintype "passive"))
    )
    (net (code "145") (name "unconnected-(P501-Pad57)") (class "Default")
      (node (ref "P501") (pin "57") (pinfunction "57_57") (pintype "passive"))
    )
    (net (code "146") (name "unconnected-(P501-Pad58)") (class "Default")
      (node (ref "P501") (pin "58") (pinfunction "58_58") (pintype "passive"))
    )
    (net (code "147") (name "unconnected-(P501-Pad59)") (class "Default")
      (node (ref "P501") (pin "59") (pinfunction "59_59") (pintype "passive"))
    )
    (net (code "148") (name "unconnected-(P501-Pad60)") (class "Default")
      (node (ref "P501") (pin "60") (pinfunction "60_60") (pintype "passive"))
    )
    (net (code "149") (name "unconnected-(P501-Pad62)") (class "Default")
      (node (ref "P501") (pin "62") (pinfunction "62_62") (pintype "passive"))
    )
    (net (code "150") (name "unconnected-(P501-Pad64)") (class "Default")
      (node (ref "P501") (pin "64") (pinfunction "64_64") (pintype "passive"))
    )
    (net (code "151") (name "unconnected-(P501-Pad65)") (class "Default")
      (node (ref "P501") (pin "65") (pinfunction "65_65") (pintype "passive"))
    )
    (net (code "152") (name "unconnected-(P501-Pad66)") (class "Default")
      (node (ref "P501") (pin "66") (pinfunction "66_66") (pintype "passive"))
    )
    (net (code "153") (name "unconnected-(P501-Pad67)") (class "Default")
      (node (ref "P501") (pin "67") (pinfunction "67_67") (pintype "passive"))
    )
    (net (code "154") (name "unconnected-(P501-Pad68)") (class "Default")
      (node (ref "P501") (pin "68") (pinfunction "68_68") (pintype "passive"))
    )
    (net (code "155") (name "unconnected-(P501-Pad69)") (class "Default")
      (node (ref "P501") (pin "69") (pinfunction "69_69") (pintype "passive"))
    )
    (net (code "156") (name "unconnected-(P501-Pad70)") (class "Default")
      (node (ref "P501") (pin "70") (pinfunction "70_70") (pintype "passive"))
    )
    (net (code "157") (name "unconnected-(P501-Pad71)") (class "Default")
      (node (ref "P501") (pin "71") (pinfunction "71_71") (pintype "passive"))
    )
    (net (code "158") (name "unconnected-(P501-Pad72)") (class "Default")
      (node (ref "P501") (pin "72") (pinfunction "72_72") (pintype "passive"))
    )
    (net (code "159") (name "unconnected-(P501-Pad73)") (class "Default")
      (node (ref "P501") (pin "73") (pinfunction "73_73") (pintype "passive"))
    )
    (net (code "160") (name "unconnected-(P501-Pad75)") (class "Default")
      (node (ref "P501") (pin "75") (pinfunction "75_75") (pintype "passive"))
    )
    (net (code "161") (name "unconnected-(P501-Pad77)") (class "Default")
      (node (ref "P501") (pin "77") (pinfunction "77_77") (pintype "passive"))
    )
    (net (code "162") (name "unconnected-(P501-Pad79)") (class "Default")
      (node (ref "P501") (pin "79") (pinfunction "79_79") (pintype "passive"))
    )
    (net (code "163") (name "unconnected-(PSM200-PadNC)") (class "Default")
      (node (ref "PSM200") (pin "NC") (pinfunction "NC_NC") (pintype "passive"))
    )
    (net (code "164") (name "unconnected-(U200-CSET-Pad6)") (class "Default")
      (node (ref "U200") (pin "6") (pinfunction "CSET_6") (pintype "passive"))
    )
    (net (code "165") (name "unconnected-(U200-POR2-Pad3)") (class "Default")
      (node (ref "U200") (pin "3") (pinfunction "POR2_3") (pintype "passive"))
    )
    (net (code "166") (name "unconnected-(U200-VOUT2-Pad7)") (class "Default")
      (node (ref "U200") (pin "7") (pinfunction "VOUT2_7") (pintype "passive"))
    )
  )
)
